# DRUM_MACHINE_SCHEMATIC.net
KiCad netlist of a schematic drawn in EAGLE
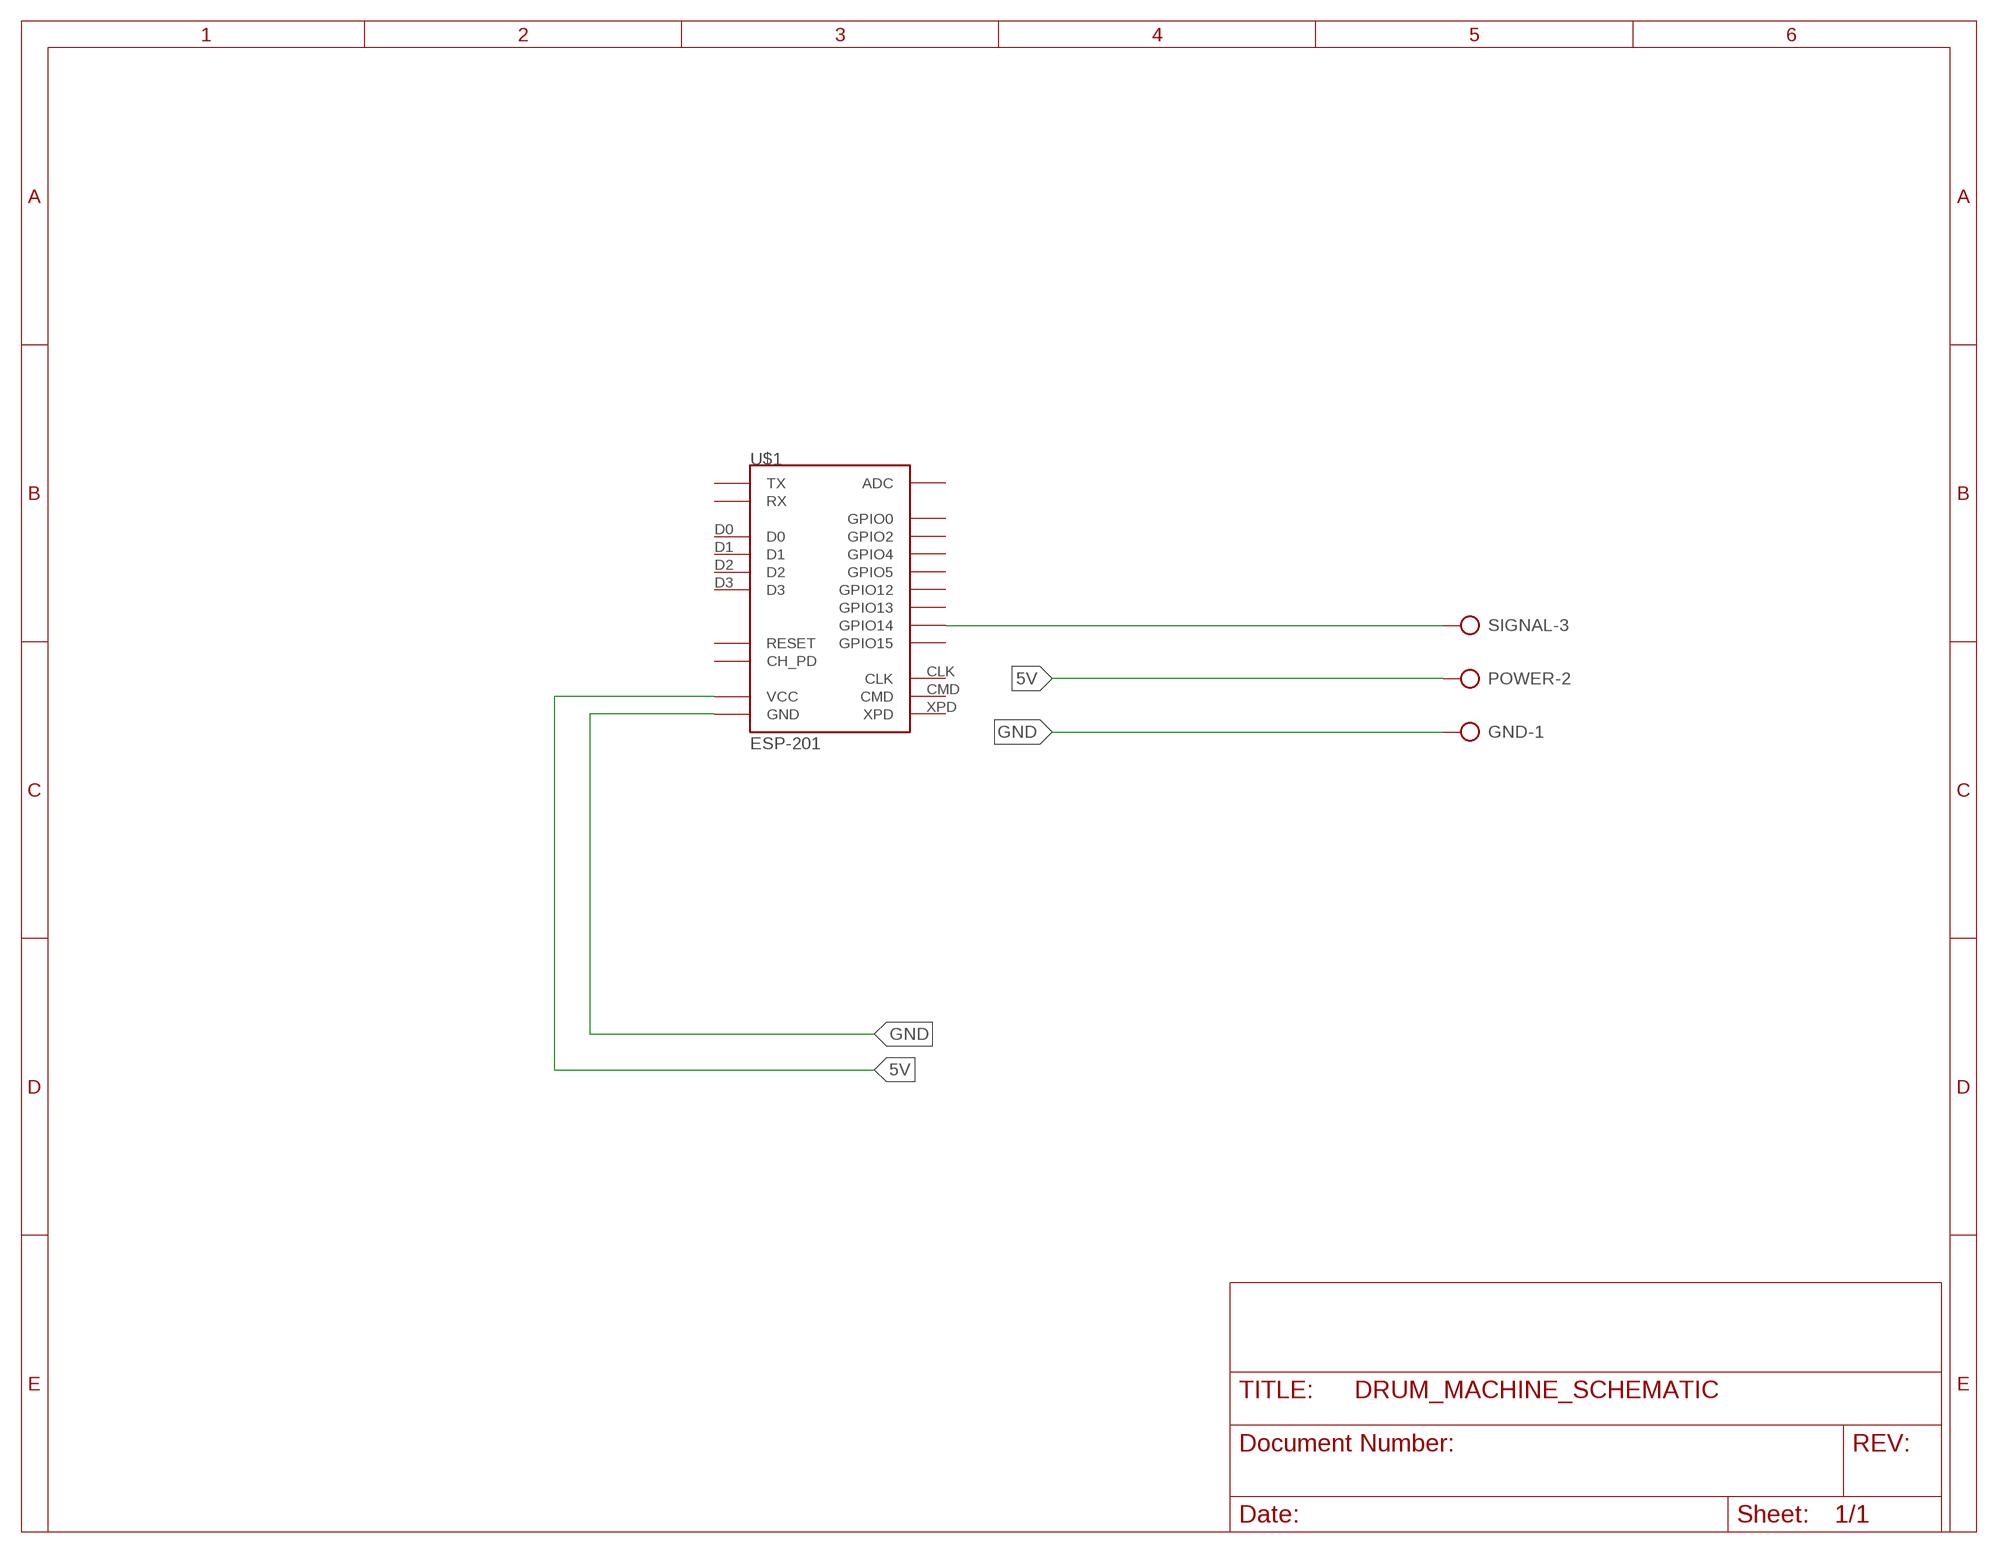
[diagram p0: schematic, sheet 1]

(export (version "E")
  (design (tool "Eeschema 10.0.6"))
  (components
    (comp (ref "GND")
      (value "AK300/2")
      (footprint "eagle-import:AK300_2")
      (libsource (lib "eagle-import") (part "AK300/2"))
    )
    (comp (ref "POWER")
      (value "AK300/2")
      (footprint "eagle-import:AK300_2")
      (libsource (lib "eagle-import") (part "AK300/2"))
    )
    (comp (ref "SIGNAL")
      (value "AK300/3")
      (footprint "eagle-import:AK300_3")
      (libsource (lib "eagle-import") (part "AK300/3"))
    )
    (comp (ref "U$1")
      (value "ESP-201")
      (footprint "eagle-import:ESP-201")
      (libsource (lib "eagle-import") (part "ESP-201"))
    )
  )
  (nets
    (net (code "1") (name "5V") (class "Default")
      (node (ref "POWER") (pin "2") (pinfunction "KL_2") (pintype "passive"))
      (node (ref "U$1") (pin "3V3") (pinfunction "VCC_3V3") (pintype "bidirectional"))
      (node (ref "U$1") (pin "3V3_2") (pinfunction "VCC_3V3_2") (pintype "bidirectional"))
      (node (ref "U$1") (pin "3V3_3") (pinfunction "VCC_3V3_3") (pintype "bidirectional"))
    )
    (net (code "2") (name "GND") (class "Default")
      (node (ref "GND") (pin "1") (pinfunction "KL_1") (pintype "passive"))
      (node (ref "U$1") (pin "GND") (pinfunction "GND_GND") (pintype "bidirectional"))
      (node (ref "U$1") (pin "GND_2") (pinfunction "GND_GND_2") (pintype "bidirectional"))
      (node (ref "U$1") (pin "GND_3") (pinfunction "GND_GND_3") (pintype "bidirectional"))
    )
    (net (code "3") (name "Net-(SIGNALC-KL)") (class "Default")
      (node (ref "SIGNAL") (pin "3") (pinfunction "KL_3") (pintype "passive"))
      (node (ref "U$1") (pin "GPIO14") (pinfunction "GPIO14_GPIO14") (pintype "bidirectional"))
    )
    (net (code "4") (name "unconnected-(U$1-PadADC)") (class "Default")
      (node (ref "U$1") (pin "ADC") (pinfunction "ADC_ADC") (pintype "bidirectional"))
    )
    (net (code "5") (name "unconnected-(U$1-PadCH_PD)") (class "Default")
      (node (ref "U$1") (pin "CH_PD") (pinfunction "CH_PD_CH_PD") (pintype "bidirectional"))
    )
    (net (code "6") (name "unconnected-(U$1-PadCLK)") (class "Default")
      (node (ref "U$1") (pin "CLK") (pinfunction "CLK_CLK") (pintype "bidirectional"))
    )
    (net (code "7") (name "unconnected-(U$1-PadCMD)") (class "Default")
      (node (ref "U$1") (pin "CMD") (pinfunction "CMD_CMD") (pintype "bidirectional"))
    )
    (net (code "8") (name "unconnected-(U$1-PadD0)") (class "Default")
      (node (ref "U$1") (pin "D0") (pinfunction "D0_D0") (pintype "bidirectional"))
    )
    (net (code "9") (name "unconnected-(U$1-PadD1)") (class "Default")
      (node (ref "U$1") (pin "D1") (pinfunction "D1_D1") (pintype "bidirectional"))
    )
    (net (code "10") (name "unconnected-(U$1-PadD2)") (class "Default")
      (node (ref "U$1") (pin "D2") (pinfunction "D2_D2") (pintype "bidirectional"))
    )
    (net (code "11") (name "unconnected-(U$1-PadD3)") (class "Default")
      (node (ref "U$1") (pin "D3") (pinfunction "D3_D3") (pintype "bidirectional"))
    )
    (net (code "12") (name "unconnected-(U$1-PadGPIO0)") (class "Default")
      (node (ref "U$1") (pin "GPIO0") (pinfunction "GPIO0_GPIO0") (pintype "bidirectional"))
    )
    (net (code "13") (name "unconnected-(U$1-PadGPIO2)") (class "Default")
      (node (ref "U$1") (pin "GPIO2") (pinfunction "GPIO2_GPIO2") (pintype "bidirectional"))
    )
    (net (code "14") (name "unconnected-(U$1-PadGPIO4)") (class "Default")
      (node (ref "U$1") (pin "GPIO4") (pinfunction "GPIO4_GPIO4") (pintype "bidirectional"))
    )
    (net (code "15") (name "unconnected-(U$1-PadGPIO5)") (class "Default")
      (node (ref "U$1") (pin "GPIO5") (pinfunction "GPIO5_GPIO5") (pintype "bidirectional"))
    )
    (net (code "16") (name "unconnected-(U$1-PadGPIO12)") (class "Default")
      (node (ref "U$1") (pin "GPIO12") (pinfunction "GPIO12_GPIO12") (pintype "bidirectional"))
    )
    (net (code "17") (name "unconnected-(U$1-PadGPIO13)") (class "Default")
      (node (ref "U$1") (pin "GPIO13") (pinfunction "GPIO13_GPIO13") (pintype "bidirectional"))
    )
    (net (code "18") (name "unconnected-(U$1-PadGPIO15)") (class "Default")
      (node (ref "U$1") (pin "GPIO15") (pinfunction "GPIO15_GPIO15") (pintype "bidirectional"))
    )
    (net (code "19") (name "unconnected-(U$1-PadRX)") (class "Default")
      (node (ref "U$1") (pin "RX") (pinfunction "RX_RX") (pintype "bidirectional"))
    )
    (net (code "20") (name "unconnected-(U$1-PadTX)") (class "Default")
      (node (ref "U$1") (pin "TX") (pinfunction "TX_TX") (pintype "bidirectional"))
    )
    (net (code "21") (name "unconnected-(U$1-PadXPD)") (class "Default")
      (node (ref "U$1") (pin "XPD") (pinfunction "XPD_XPD") (pintype "bidirectional"))
    )
    (net (code "22") (name "unconnected-(U$1-RESET-PadRST)") (class "Default")
      (node (ref "U$1") (pin "RST") (pinfunction "RESET_RST") (pintype "bidirectional"))
    )
  )
)
